# Nu6509_test.net
KiCad netlist of a schematic drawn in EAGLE
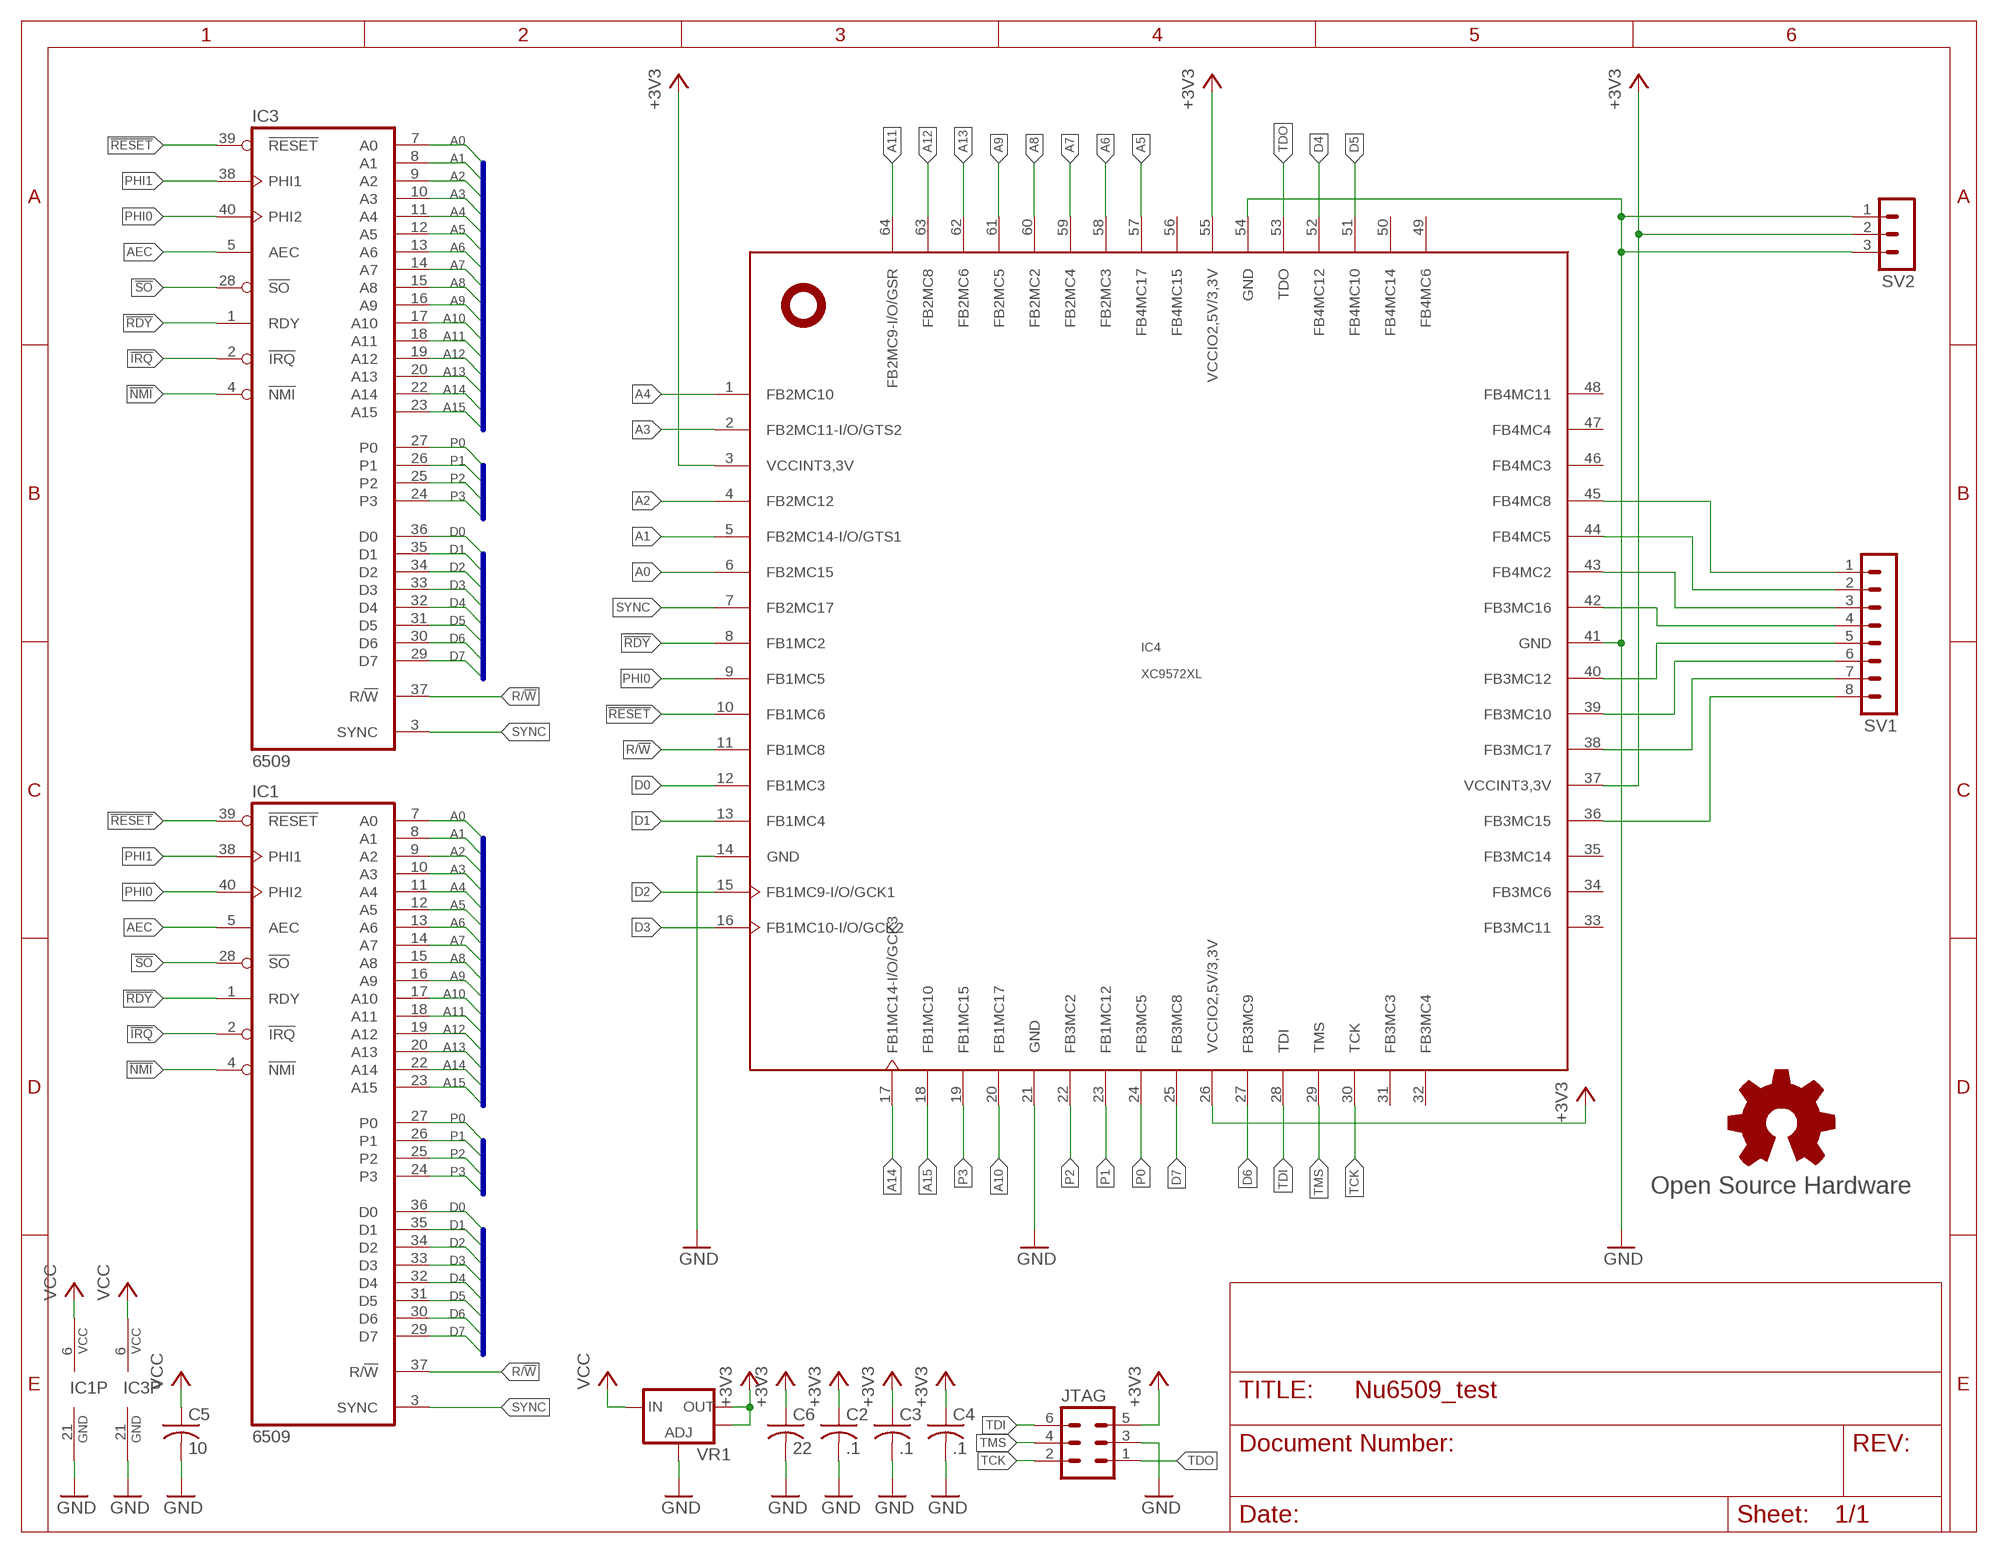
[diagram p0: schematic, sheet 1]

(export (version "E")
  (design (tool "Eeschema 10.0.6"))
  (components
    (comp (ref "C2")
      (value ".1")
      (footprint "eagle-import:C0402")
      (libsource (lib "eagle-import") (part "C-USC0402"))
    )
    (comp (ref "C3")
      (value ".1")
      (footprint "eagle-import:C0402")
      (libsource (lib "eagle-import") (part "C-USC0402"))
    )
    (comp (ref "C4")
      (value ".1")
      (footprint "eagle-import:C0402")
      (libsource (lib "eagle-import") (part "C-USC0402"))
    )
    (comp (ref "C5")
      (value "10")
      (footprint "eagle-import:C0805")
      (libsource (lib "eagle-import") (part "C-USC0805"))
    )
    (comp (ref "C6")
      (value "22")
      (footprint "eagle-import:C0805")
      (libsource (lib "eagle-import") (part "C-USC0805"))
    )
    (comp (ref "GOLD_ORB_SM1")
      (value "Open Source Hardware")
      (footprint "eagle-import:OSHW_5MM")
      (libsource (lib "eagle-import") (part "OSHWLOGOLOGO5MM"))
    )
    (comp (ref "IC1")
      (value "6509")
      (footprint "eagle-import:DIL40-ROUNDPAD")
      (libsource (lib "eagle-import") (part "6509-RP"))
    )
    (comp (ref "IC3")
      (value "6509")
      (footprint "eagle-import:DIL40-ROUNDPAD")
      (libsource (lib "eagle-import") (part "6509-RP"))
    )
    (comp (ref "IC4")
      (value "XC9572XL")
      (footprint "eagle-import:VQFP64")
      (libsource (lib "eagle-import") (part "XC9572XLVQG64"))
    )
    (comp (ref "JTAG")
      (value "MA03-2")
      (footprint "eagle-import:MA03-2")
      (libsource (lib "eagle-import") (part "MA03-2"))
    )
    (comp (ref "SV1")
      (value "MA08-1")
      (footprint "eagle-import:MA08-1")
      (libsource (lib "eagle-import") (part "MA08-1"))
    )
    (comp (ref "SV2")
      (value "MA03-1")
      (footprint "eagle-import:MA03-1")
      (libsource (lib "eagle-import") (part "MA03-1"))
    )
    (comp (ref "VR1")
      (value "V_REG_LM1117SOT223")
      (footprint "eagle-import:SOT223")
      (libsource (lib "eagle-import") (part "V_REG_LM1117SOT223"))
    )
  )
  (nets
    (net (code "1") (name "+3V3") (class "Default")
      (node (ref "C2") (pin "1") (pinfunction "1_1") (pintype "passive"))
      (node (ref "C3") (pin "1") (pinfunction "1_1") (pintype "passive"))
      (node (ref "C4") (pin "1") (pinfunction "1_1") (pintype "passive"))
      (node (ref "C6") (pin "1") (pinfunction "1_1") (pintype "passive"))
      (node (ref "IC4") (pin "26") (pinfunction "VCCIO2,5V/3,3V_26") (pintype "power_in"))
      (node (ref "IC4") (pin "3") (pinfunction "VCCINT3,3V_3") (pintype "power_in"))
      (node (ref "IC4") (pin "37") (pinfunction "VCCINT3,3V_37") (pintype "power_in"))
      (node (ref "IC4") (pin "55") (pinfunction "VCCIO2,5V/3,3V_55") (pintype "power_in"))
      (node (ref "JTAG") (pin "5") (pinfunction "5_5") (pintype "passive"))
      (node (ref "SV2") (pin "2") (pinfunction "2_2") (pintype "passive"))
      (node (ref "VR1") (pin "2") (pinfunction "OUT_2") (pintype "output"))
      (node (ref "VR1") (pin "4") (pinfunction "OUT_4") (pintype "output"))
    )
    (net (code "2") (name "/R{slash}~{W}") (class "Default")
      (node (ref "IC1") (pin "37") (pinfunction "R/~{W}_37") (pintype "output"))
      (node (ref "IC3") (pin "37") (pinfunction "R/~{W}_37") (pintype "output"))
      (node (ref "IC4") (pin "11") (pinfunction "FB1MC8_11") (pintype "bidirectional"))
    )
    (net (code "3") (name "/~{IRQ}") (class "Default")
      (node (ref "IC1") (pin "2") (pinfunction "~{IRQ}_2") (pintype "input"))
      (node (ref "IC3") (pin "2") (pinfunction "~{IRQ}_2") (pintype "input"))
    )
    (net (code "4") (name "/~{NMI}") (class "Default")
      (node (ref "IC1") (pin "4") (pinfunction "~{NMI}_4") (pintype "input"))
      (node (ref "IC3") (pin "4") (pinfunction "~{NMI}_4") (pintype "input"))
    )
    (net (code "5") (name "/~{RDY}") (class "Default")
      (node (ref "IC1") (pin "1") (pinfunction "RDY_1") (pintype "input"))
      (node (ref "IC3") (pin "1") (pinfunction "RDY_1") (pintype "input"))
      (node (ref "IC4") (pin "8") (pinfunction "FB1MC2_8") (pintype "bidirectional"))
    )
    (net (code "6") (name "/~{RESET}") (class "Default")
      (node (ref "IC1") (pin "39") (pinfunction "~{RESET}_39") (pintype "input"))
      (node (ref "IC3") (pin "39") (pinfunction "~{RESET}_39") (pintype "input"))
      (node (ref "IC4") (pin "10") (pinfunction "FB1MC6_10") (pintype "bidirectional"))
    )
    (net (code "7") (name "/~{SO}") (class "Default")
      (node (ref "IC1") (pin "28") (pinfunction "~{SO}_28") (pintype "input"))
      (node (ref "IC3") (pin "28") (pinfunction "~{SO}_28") (pintype "input"))
    )
    (net (code "8") (name "A0") (class "Default")
      (node (ref "IC1") (pin "7") (pinfunction "A0_7") (pintype "output"))
      (node (ref "IC3") (pin "7") (pinfunction "A0_7") (pintype "output"))
      (node (ref "IC4") (pin "6") (pinfunction "FB2MC15_6") (pintype "bidirectional"))
    )
    (net (code "9") (name "A1") (class "Default")
      (node (ref "IC1") (pin "8") (pinfunction "A1_8") (pintype "output"))
      (node (ref "IC3") (pin "8") (pinfunction "A1_8") (pintype "output"))
      (node (ref "IC4") (pin "5") (pinfunction "FB2MC14-I/O/GTS1_5") (pintype "bidirectional"))
    )
    (net (code "10") (name "A2") (class "Default")
      (node (ref "IC1") (pin "9") (pinfunction "A2_9") (pintype "output"))
      (node (ref "IC3") (pin "9") (pinfunction "A2_9") (pintype "output"))
      (node (ref "IC4") (pin "4") (pinfunction "FB2MC12_4") (pintype "bidirectional"))
    )
    (net (code "11") (name "A3") (class "Default")
      (node (ref "IC1") (pin "10") (pinfunction "A3_10") (pintype "output"))
      (node (ref "IC3") (pin "10") (pinfunction "A3_10") (pintype "output"))
      (node (ref "IC4") (pin "2") (pinfunction "FB2MC11-I/O/GTS2_2") (pintype "bidirectional"))
    )
    (net (code "12") (name "A4") (class "Default")
      (node (ref "IC1") (pin "11") (pinfunction "A4_11") (pintype "output"))
      (node (ref "IC3") (pin "11") (pinfunction "A4_11") (pintype "output"))
      (node (ref "IC4") (pin "1") (pinfunction "FB2MC10_1") (pintype "bidirectional"))
    )
    (net (code "13") (name "A5") (class "Default")
      (node (ref "IC1") (pin "12") (pinfunction "A5_12") (pintype "output"))
      (node (ref "IC3") (pin "12") (pinfunction "A5_12") (pintype "output"))
      (node (ref "IC4") (pin "57") (pinfunction "FB4MC17_57") (pintype "bidirectional"))
    )
    (net (code "14") (name "A6") (class "Default")
      (node (ref "IC1") (pin "13") (pinfunction "A6_13") (pintype "output"))
      (node (ref "IC3") (pin "13") (pinfunction "A6_13") (pintype "output"))
      (node (ref "IC4") (pin "58") (pinfunction "FB2MC3_58") (pintype "bidirectional"))
    )
    (net (code "15") (name "A7") (class "Default")
      (node (ref "IC1") (pin "14") (pinfunction "A7_14") (pintype "output"))
      (node (ref "IC3") (pin "14") (pinfunction "A7_14") (pintype "output"))
      (node (ref "IC4") (pin "59") (pinfunction "FB2MC4_59") (pintype "bidirectional"))
    )
    (net (code "16") (name "A8") (class "Default")
      (node (ref "IC1") (pin "15") (pinfunction "A8_15") (pintype "output"))
      (node (ref "IC3") (pin "15") (pinfunction "A8_15") (pintype "output"))
      (node (ref "IC4") (pin "60") (pinfunction "FB2MC2_60") (pintype "bidirectional"))
    )
    (net (code "17") (name "A9") (class "Default")
      (node (ref "IC1") (pin "16") (pinfunction "A9_16") (pintype "output"))
      (node (ref "IC3") (pin "16") (pinfunction "A9_16") (pintype "output"))
      (node (ref "IC4") (pin "61") (pinfunction "FB2MC5_61") (pintype "bidirectional"))
    )
    (net (code "18") (name "A10") (class "Default")
      (node (ref "IC1") (pin "17") (pinfunction "A10_17") (pintype "output"))
      (node (ref "IC3") (pin "17") (pinfunction "A10_17") (pintype "output"))
      (node (ref "IC4") (pin "20") (pinfunction "FB1MC17_20") (pintype "bidirectional"))
    )
    (net (code "19") (name "A11") (class "Default")
      (node (ref "IC1") (pin "18") (pinfunction "A11_18") (pintype "output"))
      (node (ref "IC3") (pin "18") (pinfunction "A11_18") (pintype "output"))
      (node (ref "IC4") (pin "64") (pinfunction "FB2MC9-I/O/GSR_64") (pintype "bidirectional"))
    )
    (net (code "20") (name "A12") (class "Default")
      (node (ref "IC1") (pin "19") (pinfunction "A12_19") (pintype "output"))
      (node (ref "IC3") (pin "19") (pinfunction "A12_19") (pintype "output"))
      (node (ref "IC4") (pin "63") (pinfunction "FB2MC8_63") (pintype "bidirectional"))
    )
    (net (code "21") (name "A13") (class "Default")
      (node (ref "IC1") (pin "20") (pinfunction "A13_20") (pintype "output"))
      (node (ref "IC3") (pin "20") (pinfunction "A13_20") (pintype "output"))
      (node (ref "IC4") (pin "62") (pinfunction "FB2MC6_62") (pintype "bidirectional"))
    )
    (net (code "22") (name "A14") (class "Default")
      (node (ref "IC1") (pin "22") (pinfunction "A14_22") (pintype "output"))
      (node (ref "IC3") (pin "22") (pinfunction "A14_22") (pintype "output"))
      (node (ref "IC4") (pin "17") (pinfunction "FB1MC14-I/O/GCK3_17") (pintype "bidirectional"))
    )
    (net (code "23") (name "A15") (class "Default")
      (node (ref "IC1") (pin "23") (pinfunction "A15_23") (pintype "output"))
      (node (ref "IC3") (pin "23") (pinfunction "A15_23") (pintype "output"))
      (node (ref "IC4") (pin "18") (pinfunction "FB1MC10_18") (pintype "bidirectional"))
    )
    (net (code "24") (name "AEC") (class "Default")
      (node (ref "IC1") (pin "5") (pinfunction "AEC_5") (pintype "input"))
      (node (ref "IC3") (pin "5") (pinfunction "AEC_5") (pintype "input"))
    )
    (net (code "25") (name "D0") (class "Default")
      (node (ref "IC1") (pin "36") (pinfunction "D0_36") (pintype "bidirectional"))
      (node (ref "IC3") (pin "36") (pinfunction "D0_36") (pintype "bidirectional"))
      (node (ref "IC4") (pin "12") (pinfunction "FB1MC3_12") (pintype "bidirectional"))
    )
    (net (code "26") (name "D1") (class "Default")
      (node (ref "IC1") (pin "35") (pinfunction "D1_35") (pintype "bidirectional"))
      (node (ref "IC3") (pin "35") (pinfunction "D1_35") (pintype "bidirectional"))
      (node (ref "IC4") (pin "13") (pinfunction "FB1MC4_13") (pintype "bidirectional"))
    )
    (net (code "27") (name "D2") (class "Default")
      (node (ref "IC1") (pin "34") (pinfunction "D2_34") (pintype "bidirectional"))
      (node (ref "IC3") (pin "34") (pinfunction "D2_34") (pintype "bidirectional"))
      (node (ref "IC4") (pin "15") (pinfunction "FB1MC9-I/O/GCK1_15") (pintype "bidirectional"))
    )
    (net (code "28") (name "D3") (class "Default")
      (node (ref "IC1") (pin "33") (pinfunction "D3_33") (pintype "bidirectional"))
      (node (ref "IC3") (pin "33") (pinfunction "D3_33") (pintype "bidirectional"))
      (node (ref "IC4") (pin "16") (pinfunction "FB1MC10-I/O/GCK2_16") (pintype "bidirectional"))
    )
    (net (code "29") (name "D4") (class "Default")
      (node (ref "IC1") (pin "32") (pinfunction "D4_32") (pintype "bidirectional"))
      (node (ref "IC3") (pin "32") (pinfunction "D4_32") (pintype "bidirectional"))
      (node (ref "IC4") (pin "52") (pinfunction "FB4MC12_52") (pintype "bidirectional"))
    )
    (net (code "30") (name "D5") (class "Default")
      (node (ref "IC1") (pin "31") (pinfunction "D5_31") (pintype "bidirectional"))
      (node (ref "IC3") (pin "31") (pinfunction "D5_31") (pintype "bidirectional"))
      (node (ref "IC4") (pin "51") (pinfunction "FB4MC10_51") (pintype "bidirectional"))
    )
    (net (code "31") (name "D6") (class "Default")
      (node (ref "IC1") (pin "30") (pinfunction "D6_30") (pintype "bidirectional"))
      (node (ref "IC3") (pin "30") (pinfunction "D6_30") (pintype "bidirectional"))
      (node (ref "IC4") (pin "27") (pinfunction "FB3MC9_27") (pintype "bidirectional"))
    )
    (net (code "32") (name "D7") (class "Default")
      (node (ref "IC1") (pin "29") (pinfunction "D7_29") (pintype "bidirectional"))
      (node (ref "IC3") (pin "29") (pinfunction "D7_29") (pintype "bidirectional"))
      (node (ref "IC4") (pin "25") (pinfunction "FB3MC8_25") (pintype "bidirectional"))
    )
    (net (code "33") (name "GND") (class "Default")
      (node (ref "C2") (pin "2") (pinfunction "2_2") (pintype "passive"))
      (node (ref "C3") (pin "2") (pinfunction "2_2") (pintype "passive"))
      (node (ref "C4") (pin "2") (pinfunction "2_2") (pintype "passive"))
      (node (ref "C5") (pin "2") (pinfunction "2_2") (pintype "passive"))
      (node (ref "C6") (pin "2") (pinfunction "2_2") (pintype "passive"))
      (node (ref "IC1") (pin "21") (pinfunction "GND_21") (pintype "power_in"))
      (node (ref "IC3") (pin "21") (pinfunction "GND_21") (pintype "power_in"))
      (node (ref "IC4") (pin "14") (pinfunction "GND_14") (pintype "power_in"))
      (node (ref "IC4") (pin "21") (pinfunction "GND_21") (pintype "power_in"))
      (node (ref "IC4") (pin "41") (pinfunction "GND_41") (pintype "power_in"))
      (node (ref "IC4") (pin "54") (pinfunction "GND_54") (pintype "power_in"))
      (node (ref "JTAG") (pin "3") (pinfunction "3_3") (pintype "passive"))
      (node (ref "SV2") (pin "1") (pinfunction "1_1") (pintype "passive"))
      (node (ref "SV2") (pin "3") (pinfunction "3_3") (pintype "passive"))
      (node (ref "VR1") (pin "1") (pinfunction "ADJ_1") (pintype "input"))
    )
    (net (code "34") (name "Net-(IC4-FB3MC10)") (class "Default")
      (node (ref "IC4") (pin "39") (pinfunction "FB3MC10_39") (pintype "bidirectional"))
      (node (ref "SV1") (pin "6") (pinfunction "6_6") (pintype "passive"))
    )
    (net (code "35") (name "Net-(IC4-FB3MC12)") (class "Default")
      (node (ref "IC4") (pin "40") (pinfunction "FB3MC12_40") (pintype "bidirectional"))
      (node (ref "SV1") (pin "5") (pinfunction "5_5") (pintype "passive"))
    )
    (net (code "36") (name "Net-(IC4-FB3MC15)") (class "Default")
      (node (ref "IC4") (pin "36") (pinfunction "FB3MC15_36") (pintype "bidirectional"))
      (node (ref "SV1") (pin "8") (pinfunction "8_8") (pintype "passive"))
    )
    (net (code "37") (name "Net-(IC4-FB3MC16)") (class "Default")
      (node (ref "IC4") (pin "42") (pinfunction "FB3MC16_42") (pintype "bidirectional"))
      (node (ref "SV1") (pin "4") (pinfunction "4_4") (pintype "passive"))
    )
    (net (code "38") (name "Net-(IC4-FB3MC17)") (class "Default")
      (node (ref "IC4") (pin "38") (pinfunction "FB3MC17_38") (pintype "bidirectional"))
      (node (ref "SV1") (pin "7") (pinfunction "7_7") (pintype "passive"))
    )
    (net (code "39") (name "Net-(IC4-FB4MC2)") (class "Default")
      (node (ref "IC4") (pin "43") (pinfunction "FB4MC2_43") (pintype "bidirectional"))
      (node (ref "SV1") (pin "3") (pinfunction "3_3") (pintype "passive"))
    )
    (net (code "40") (name "Net-(IC4-FB4MC5)") (class "Default")
      (node (ref "IC4") (pin "44") (pinfunction "FB4MC5_44") (pintype "bidirectional"))
      (node (ref "SV1") (pin "2") (pinfunction "2_2") (pintype "passive"))
    )
    (net (code "41") (name "Net-(IC4-FB4MC8)") (class "Default")
      (node (ref "IC4") (pin "45") (pinfunction "FB4MC8_45") (pintype "bidirectional"))
      (node (ref "SV1") (pin "1") (pinfunction "1_1") (pintype "passive"))
    )
    (net (code "42") (name "P0") (class "Default")
      (node (ref "IC1") (pin "27") (pinfunction "P0_27") (pintype "output"))
      (node (ref "IC3") (pin "27") (pinfunction "P0_27") (pintype "output"))
      (node (ref "IC4") (pin "24") (pinfunction "FB3MC5_24") (pintype "bidirectional"))
    )
    (net (code "43") (name "P1") (class "Default")
      (node (ref "IC1") (pin "26") (pinfunction "P1_26") (pintype "output"))
      (node (ref "IC3") (pin "26") (pinfunction "P1_26") (pintype "output"))
      (node (ref "IC4") (pin "23") (pinfunction "FB1MC12_23") (pintype "bidirectional"))
    )
    (net (code "44") (name "P2") (class "Default")
      (node (ref "IC1") (pin "25") (pinfunction "P2_25") (pintype "output"))
      (node (ref "IC3") (pin "25") (pinfunction "P2_25") (pintype "output"))
      (node (ref "IC4") (pin "22") (pinfunction "FB3MC2_22") (pintype "bidirectional"))
    )
    (net (code "45") (name "P3") (class "Default")
      (node (ref "IC1") (pin "24") (pinfunction "P3_24") (pintype "output"))
      (node (ref "IC3") (pin "24") (pinfunction "P3_24") (pintype "output"))
      (node (ref "IC4") (pin "19") (pinfunction "FB1MC15_19") (pintype "bidirectional"))
    )
    (net (code "46") (name "PHI0") (class "Default")
      (node (ref "IC1") (pin "40") (pinfunction "PHI2_40") (pintype "input"))
      (node (ref "IC3") (pin "40") (pinfunction "PHI2_40") (pintype "input"))
      (node (ref "IC4") (pin "9") (pinfunction "FB1MC5_9") (pintype "bidirectional"))
    )
    (net (code "47") (name "PHI1") (class "Default")
      (node (ref "IC1") (pin "38") (pinfunction "PHI1_38") (pintype "input"))
      (node (ref "IC3") (pin "38") (pinfunction "PHI1_38") (pintype "input"))
    )
    (net (code "48") (name "SYNC") (class "Default")
      (node (ref "IC1") (pin "3") (pinfunction "SYNC_3") (pintype "output"))
      (node (ref "IC3") (pin "3") (pinfunction "SYNC_3") (pintype "output"))
      (node (ref "IC4") (pin "7") (pinfunction "FB2MC17_7") (pintype "bidirectional"))
    )
    (net (code "49") (name "TCK") (class "Default")
      (node (ref "IC4") (pin "30") (pinfunction "TCK_30") (pintype "bidirectional"))
      (node (ref "JTAG") (pin "2") (pinfunction "2_2") (pintype "passive"))
    )
    (net (code "50") (name "TDI") (class "Default")
      (node (ref "IC4") (pin "28") (pinfunction "TDI_28") (pintype "bidirectional"))
      (node (ref "JTAG") (pin "6") (pinfunction "6_6") (pintype "passive"))
    )
    (net (code "51") (name "TDO") (class "Default")
      (node (ref "IC4") (pin "53") (pinfunction "TDO_53") (pintype "bidirectional"))
      (node (ref "JTAG") (pin "1") (pinfunction "1_1") (pintype "passive"))
    )
    (net (code "52") (name "TMS") (class "Default")
      (node (ref "IC4") (pin "29") (pinfunction "TMS_29") (pintype "bidirectional"))
      (node (ref "JTAG") (pin "4") (pinfunction "4_4") (pintype "passive"))
    )
    (net (code "53") (name "VCC") (class "Default")
      (node (ref "C5") (pin "1") (pinfunction "1_1") (pintype "passive"))
      (node (ref "IC1") (pin "6") (pinfunction "VCC_6") (pintype "power_in"))
      (node (ref "IC3") (pin "6") (pinfunction "VCC_6") (pintype "power_in"))
      (node (ref "VR1") (pin "3") (pinfunction "IN_3") (pintype "input"))
    )
    (net (code "54") (name "unconnected-(IC4-FB3MC3-Pad31)") (class "Default")
      (node (ref "IC4") (pin "31") (pinfunction "FB3MC3_31") (pintype "bidirectional"))
    )
    (net (code "55") (name "unconnected-(IC4-FB3MC4-Pad32)") (class "Default")
      (node (ref "IC4") (pin "32") (pinfunction "FB3MC4_32") (pintype "bidirectional"))
    )
    (net (code "56") (name "unconnected-(IC4-FB3MC6-Pad34)") (class "Default")
      (node (ref "IC4") (pin "34") (pinfunction "FB3MC6_34") (pintype "bidirectional"))
    )
    (net (code "57") (name "unconnected-(IC4-FB3MC11-Pad33)") (class "Default")
      (node (ref "IC4") (pin "33") (pinfunction "FB3MC11_33") (pintype "bidirectional"))
    )
    (net (code "58") (name "unconnected-(IC4-FB3MC14-Pad35)") (class "Default")
      (node (ref "IC4") (pin "35") (pinfunction "FB3MC14_35") (pintype "bidirectional"))
    )
    (net (code "59") (name "unconnected-(IC4-FB4MC3-Pad46)") (class "Default")
      (node (ref "IC4") (pin "46") (pinfunction "FB4MC3_46") (pintype "bidirectional"))
    )
    (net (code "60") (name "unconnected-(IC4-FB4MC4-Pad47)") (class "Default")
      (node (ref "IC4") (pin "47") (pinfunction "FB4MC4_47") (pintype "bidirectional"))
    )
    (net (code "61") (name "unconnected-(IC4-FB4MC6-Pad49)") (class "Default")
      (node (ref "IC4") (pin "49") (pinfunction "FB4MC6_49") (pintype "bidirectional"))
    )
    (net (code "62") (name "unconnected-(IC4-FB4MC11-Pad48)") (class "Default")
      (node (ref "IC4") (pin "48") (pinfunction "FB4MC11_48") (pintype "bidirectional"))
    )
    (net (code "63") (name "unconnected-(IC4-FB4MC14-Pad50)") (class "Default")
      (node (ref "IC4") (pin "50") (pinfunction "FB4MC14_50") (pintype "bidirectional"))
    )
    (net (code "64") (name "unconnected-(IC4-FB4MC15-Pad56)") (class "Default")
      (node (ref "IC4") (pin "56") (pinfunction "FB4MC15_56") (pintype "bidirectional"))
    )
  )
)
